# supply1.net
KiCad netlist of a schematic drawn in EAGLE
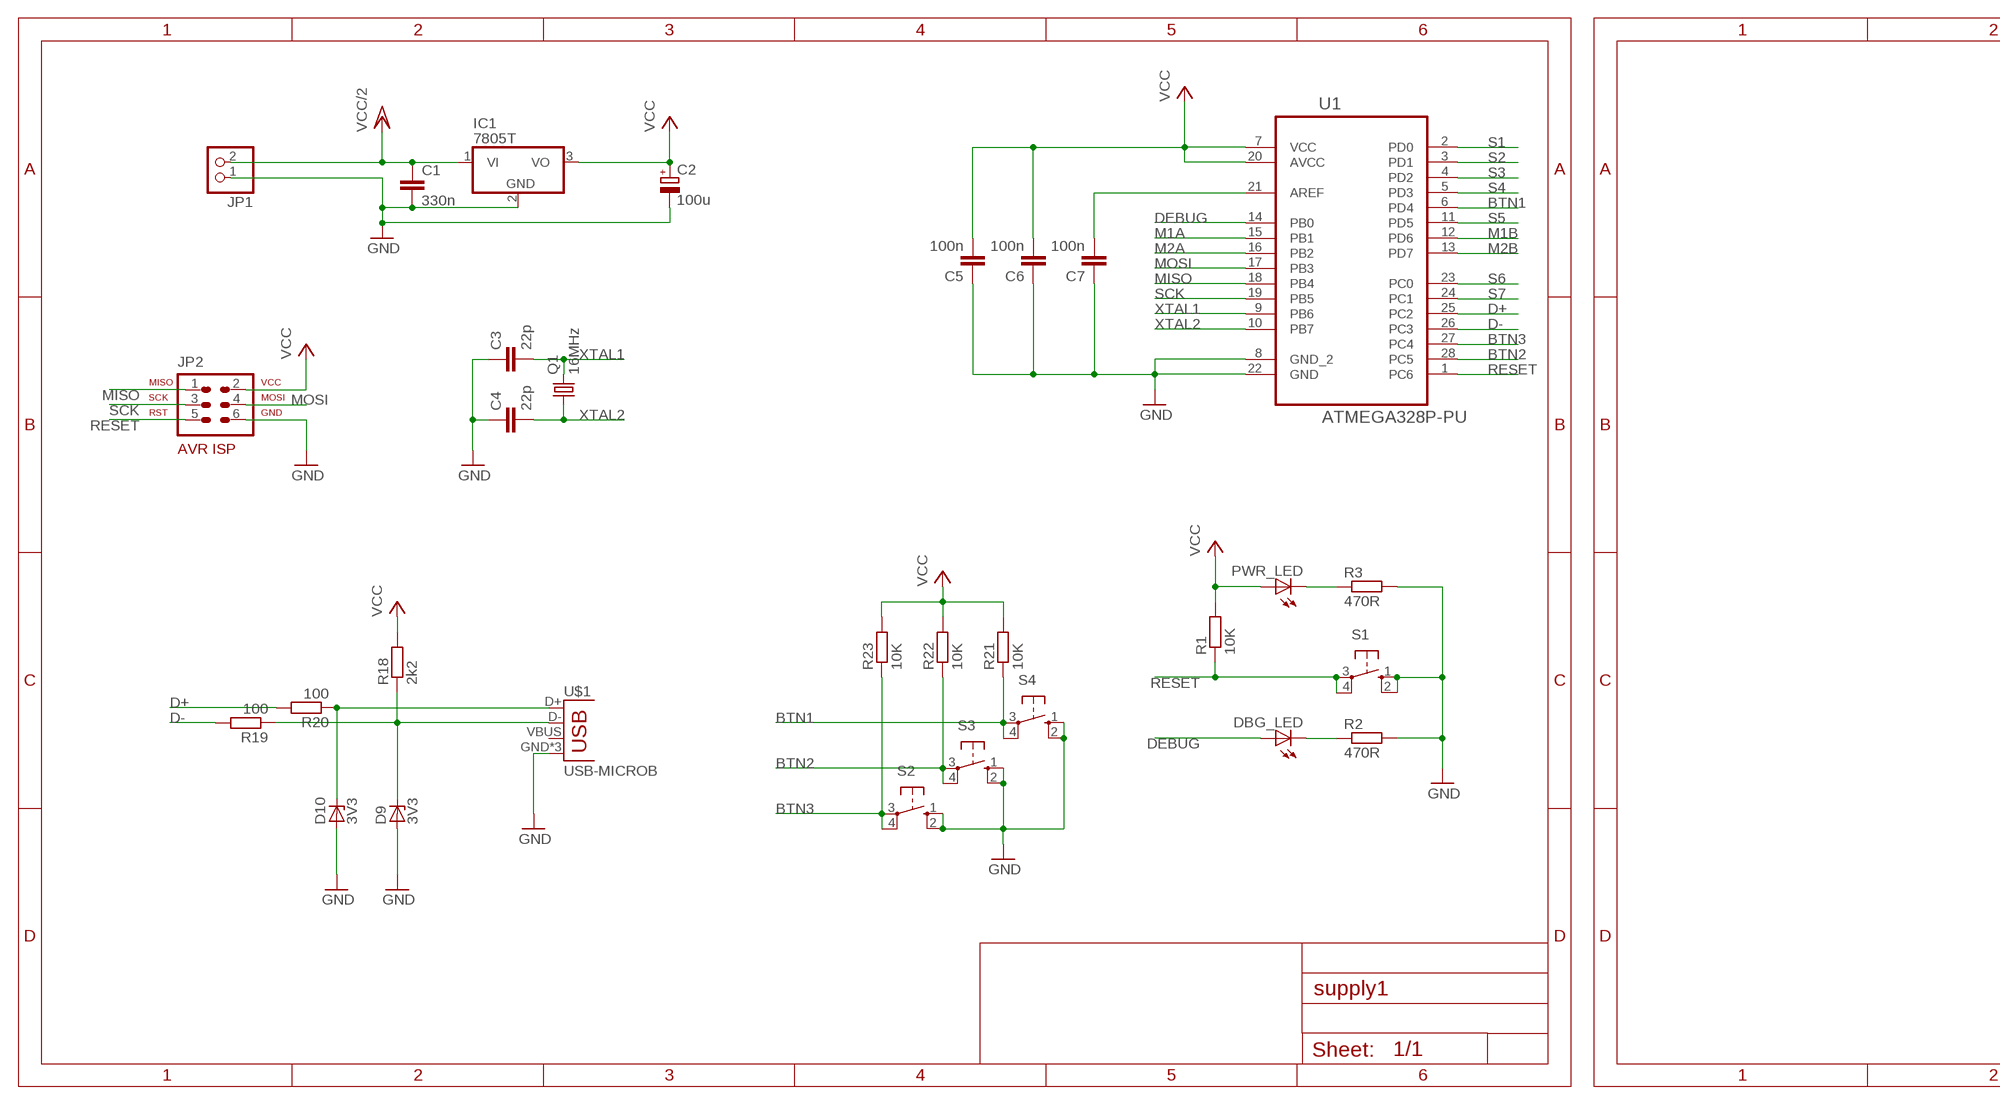
[diagram p0: schematic, sheet 1, part 1 of 2]
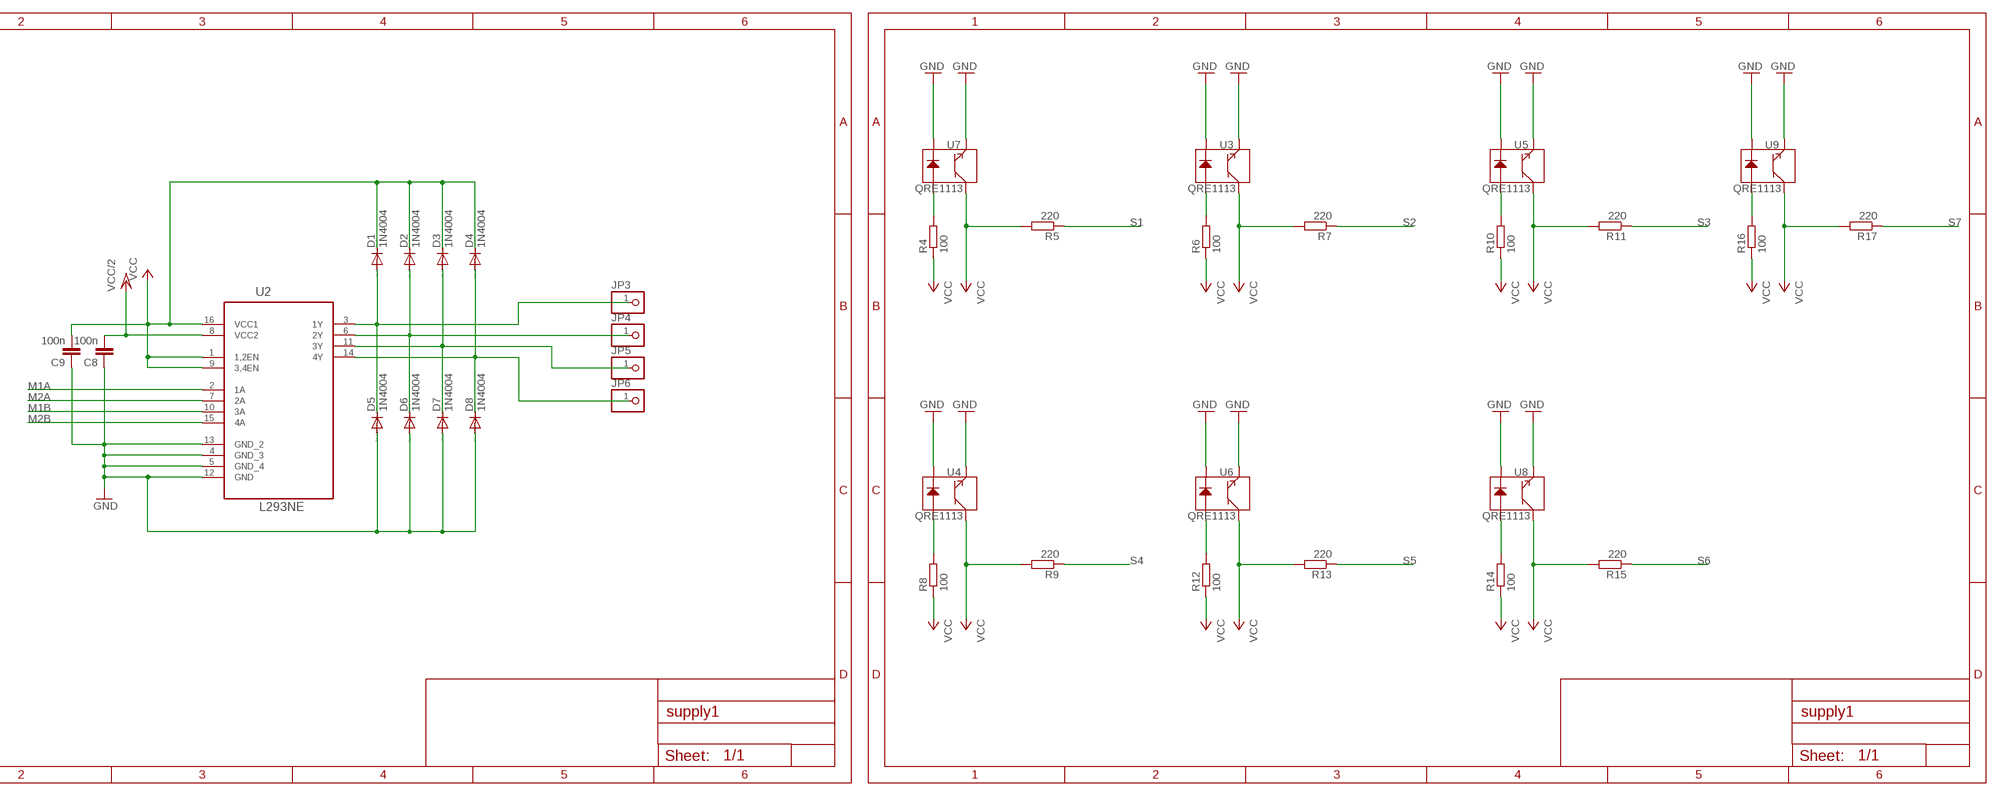
[diagram p1: schematic, sheet 1, part 2 of 2]

(export (version "E")
  (design (tool "Eeschema 10.0.6"))
  (components
    (comp (ref "C1")
      (value "330n")
      (footprint "eagle-import:C1206K")
      (libsource (lib "eagle-import") (part "C-EUC1206K"))
    )
    (comp (ref "C2")
      (value "100u")
      (footprint "eagle-import:E2,5-5")
      (libsource (lib "eagle-import") (part "CPOL-EUE2.5-5"))
    )
    (comp (ref "C3")
      (value "22p")
      (footprint "eagle-import:C0805K")
      (libsource (lib "eagle-import") (part "C-EUC0805K"))
    )
    (comp (ref "C4")
      (value "22p")
      (footprint "eagle-import:C0805K")
      (libsource (lib "eagle-import") (part "C-EUC0805K"))
    )
    (comp (ref "C5")
      (value "100n")
      (footprint "eagle-import:C0805K")
      (libsource (lib "eagle-import") (part "C-EUC0805K"))
    )
    (comp (ref "C6")
      (value "100n")
      (footprint "eagle-import:C0805K")
      (libsource (lib "eagle-import") (part "C-EUC0805K"))
    )
    (comp (ref "C7")
      (value "100n")
      (footprint "eagle-import:C0805K")
      (libsource (lib "eagle-import") (part "C-EUC0805K"))
    )
    (comp (ref "C8")
      (value "100n")
      (footprint "eagle-import:C0805K")
      (libsource (lib "eagle-import") (part "C-EUC0805K"))
    )
    (comp (ref "C9")
      (value "100n")
      (footprint "eagle-import:C0805K")
      (libsource (lib "eagle-import") (part "C-EUC0805K"))
    )
    (comp (ref "D1")
      (value "1N4004")
      (footprint "eagle-import:DO41-10")
      (libsource (lib "eagle-import") (part "1N4004"))
    )
    (comp (ref "D2")
      (value "1N4004")
      (footprint "eagle-import:DO41-10")
      (libsource (lib "eagle-import") (part "1N4004"))
    )
    (comp (ref "D3")
      (value "1N4004")
      (footprint "eagle-import:DO41-10")
      (libsource (lib "eagle-import") (part "1N4004"))
    )
    (comp (ref "D4")
      (value "1N4004")
      (footprint "eagle-import:DO41-10")
      (libsource (lib "eagle-import") (part "1N4004"))
    )
    (comp (ref "D5")
      (value "1N4004")
      (footprint "eagle-import:DO41-10")
      (libsource (lib "eagle-import") (part "1N4004"))
    )
    (comp (ref "D6")
      (value "1N4004")
      (footprint "eagle-import:DO41-10")
      (libsource (lib "eagle-import") (part "1N4004"))
    )
    (comp (ref "D7")
      (value "1N4004")
      (footprint "eagle-import:DO41-10")
      (libsource (lib "eagle-import") (part "1N4004"))
    )
    (comp (ref "D8")
      (value "1N4004")
      (footprint "eagle-import:DO41-10")
      (libsource (lib "eagle-import") (part "1N4004"))
    )
    (comp (ref "D9")
      (value "3V3")
      (footprint "eagle-import:DO41Z10")
      (libsource (lib "eagle-import") (part "ZENER-DIODEDO41Z10"))
    )
    (comp (ref "D10")
      (value "3V3")
      (footprint "eagle-import:DO41Z10")
      (libsource (lib "eagle-import") (part "ZENER-DIODEDO41Z10"))
    )
    (comp (ref "DBG_LED")
      (value "LED5MM")
      (footprint "eagle-import:LED5MM")
      (libsource (lib "eagle-import") (part "LED5MM"))
    )
    (comp (ref "IC1")
      (value "7805T")
      (footprint "eagle-import:TO220H")
      (libsource (lib "eagle-import") (part "78T05"))
    )
    (comp (ref "JP1")
      (value "PINHD-1X2")
      (footprint "eagle-import:1X02")
      (libsource (lib "eagle-import") (part "PINHD-1X2"))
    )
    (comp (ref "JP2")
      (value "AVR-ISP-6VERT")
      (footprint "eagle-import:AVR-ISP-6")
      (libsource (lib "eagle-import") (part "AVR-ISP-6VERT"))
    )
    (comp (ref "JP3")
      (value "PINHD-1X1")
      (footprint "eagle-import:1X01")
      (libsource (lib "eagle-import") (part "PINHD-1X1"))
    )
    (comp (ref "JP4")
      (value "PINHD-1X1")
      (footprint "eagle-import:1X01")
      (libsource (lib "eagle-import") (part "PINHD-1X1"))
    )
    (comp (ref "JP5")
      (value "PINHD-1X1")
      (footprint "eagle-import:1X01")
      (libsource (lib "eagle-import") (part "PINHD-1X1"))
    )
    (comp (ref "JP6")
      (value "PINHD-1X1")
      (footprint "eagle-import:1X01")
      (libsource (lib "eagle-import") (part "PINHD-1X1"))
    )
    (comp (ref "PWR_LED")
      (value "LED5MM")
      (footprint "eagle-import:LED5MM")
      (libsource (lib "eagle-import") (part "LED5MM"))
    )
    (comp (ref "Q1")
      (value "16MHz")
      (footprint "eagle-import:HC49_S")
      (libsource (lib "eagle-import") (part "CRYSTALHC49S"))
    )
    (comp (ref "R1")
      (value "10K")
      (footprint "eagle-import:M0805")
      (libsource (lib "eagle-import") (part "R-EU_M0805"))
    )
    (comp (ref "R2")
      (value "470R")
      (footprint "eagle-import:M0805")
      (libsource (lib "eagle-import") (part "R-EU_M0805"))
    )
    (comp (ref "R3")
      (value "470R")
      (footprint "eagle-import:M0805")
      (libsource (lib "eagle-import") (part "R-EU_M0805"))
    )
    (comp (ref "R4")
      (value "100")
      (footprint "eagle-import:M0805")
      (libsource (lib "eagle-import") (part "R-EU_M0805"))
    )
    (comp (ref "R5")
      (value "220")
      (footprint "eagle-import:M0805")
      (libsource (lib "eagle-import") (part "R-EU_M0805"))
    )
    (comp (ref "R6")
      (value "100")
      (footprint "eagle-import:M0805")
      (libsource (lib "eagle-import") (part "R-EU_M0805"))
    )
    (comp (ref "R7")
      (value "220")
      (footprint "eagle-import:M0805")
      (libsource (lib "eagle-import") (part "R-EU_M0805"))
    )
    (comp (ref "R8")
      (value "100")
      (footprint "eagle-import:M0805")
      (libsource (lib "eagle-import") (part "R-EU_M0805"))
    )
    (comp (ref "R9")
      (value "220")
      (footprint "eagle-import:M0805")
      (libsource (lib "eagle-import") (part "R-EU_M0805"))
    )
    (comp (ref "R10")
      (value "100")
      (footprint "eagle-import:M0805")
      (libsource (lib "eagle-import") (part "R-EU_M0805"))
    )
    (comp (ref "R11")
      (value "220")
      (footprint "eagle-import:M0805")
      (libsource (lib "eagle-import") (part "R-EU_M0805"))
    )
    (comp (ref "R12")
      (value "100")
      (footprint "eagle-import:M0805")
      (libsource (lib "eagle-import") (part "R-EU_M0805"))
    )
    (comp (ref "R13")
      (value "220")
      (footprint "eagle-import:M0805")
      (libsource (lib "eagle-import") (part "R-EU_M0805"))
    )
    (comp (ref "R14")
      (value "100")
      (footprint "eagle-import:M0805")
      (libsource (lib "eagle-import") (part "R-EU_M0805"))
    )
    (comp (ref "R15")
      (value "220")
      (footprint "eagle-import:M0805")
      (libsource (lib "eagle-import") (part "R-EU_M0805"))
    )
    (comp (ref "R16")
      (value "100")
      (footprint "eagle-import:M0805")
      (libsource (lib "eagle-import") (part "R-EU_M0805"))
    )
    (comp (ref "R17")
      (value "220")
      (footprint "eagle-import:M0805")
      (libsource (lib "eagle-import") (part "R-EU_M0805"))
    )
    (comp (ref "R18")
      (value "2k2")
      (footprint "eagle-import:M0805")
      (libsource (lib "eagle-import") (part "R-EU_M0805"))
    )
    (comp (ref "R19")
      (value "100")
      (footprint "eagle-import:M0805")
      (libsource (lib "eagle-import") (part "R-EU_M0805"))
    )
    (comp (ref "R20")
      (value "100")
      (footprint "eagle-import:M0805")
      (libsource (lib "eagle-import") (part "R-EU_M0805"))
    )
    (comp (ref "R21")
      (value "10K")
      (footprint "eagle-import:M0805")
      (libsource (lib "eagle-import") (part "R-EU_M0805"))
    )
    (comp (ref "R22")
      (value "10K")
      (footprint "eagle-import:M0805")
      (libsource (lib "eagle-import") (part "R-EU_M0805"))
    )
    (comp (ref "R23")
      (value "10K")
      (footprint "eagle-import:M0805")
      (libsource (lib "eagle-import") (part "R-EU_M0805"))
    )
    (comp (ref "S1")
      (value "10-XX")
      (footprint "eagle-import:B3F-10XX")
      (fields (field (name "MPN") "B3F-1000"))
      (libsource (lib "eagle-import") (part "10-XX"))
    )
    (comp (ref "S2")
      (value "10-XX")
      (footprint "eagle-import:B3F-10XX")
      (fields (field (name "MPN") "B3F-1000"))
      (libsource (lib "eagle-import") (part "10-XX"))
    )
    (comp (ref "S3")
      (value "10-XX")
      (footprint "eagle-import:B3F-10XX")
      (fields (field (name "MPN") "B3F-1000"))
      (libsource (lib "eagle-import") (part "10-XX"))
    )
    (comp (ref "S4")
      (value "10-XX")
      (footprint "eagle-import:B3F-10XX")
      (fields (field (name "MPN") "B3F-1000"))
      (libsource (lib "eagle-import") (part "10-XX"))
    )
    (comp (ref "U$1")
      (value "USB-MICROB")
      (footprint "eagle-import:USB-MICROB")
      (libsource (lib "eagle-import") (part "USB-MICROB"))
    )
    (comp (ref "U1")
      (value "ATMEGA328P-PU")
      (footprint "eagle-import:DIP254P762X457-28")
      (libsource (lib "eagle-import") (part "ATMEGA328P-PU"))
    )
    (comp (ref "U2")
      (value "L293NE")
      (footprint "eagle-import:DIP254P762X508-16")
      (libsource (lib "eagle-import") (part "L293NE"))
    )
    (comp (ref "U3")
      (value "QRE1113")
      (footprint "eagle-import:QRE1113")
      (libsource (lib "eagle-import") (part "QRE1113"))
    )
    (comp (ref "U4")
      (value "QRE1113")
      (footprint "eagle-import:QRE1113")
      (libsource (lib "eagle-import") (part "QRE1113"))
    )
    (comp (ref "U5")
      (value "QRE1113")
      (footprint "eagle-import:QRE1113")
      (libsource (lib "eagle-import") (part "QRE1113"))
    )
    (comp (ref "U6")
      (value "QRE1113")
      (footprint "eagle-import:QRE1113")
      (libsource (lib "eagle-import") (part "QRE1113"))
    )
    (comp (ref "U7")
      (value "QRE1113")
      (footprint "eagle-import:QRE1113")
      (libsource (lib "eagle-import") (part "QRE1113"))
    )
    (comp (ref "U8")
      (value "QRE1113")
      (footprint "eagle-import:QRE1113")
      (libsource (lib "eagle-import") (part "QRE1113"))
    )
    (comp (ref "U9")
      (value "QRE1113")
      (footprint "eagle-import:QRE1113")
      (libsource (lib "eagle-import") (part "QRE1113"))
    )
  )
  (nets
    (net (code "1") (name "/BTN1") (class "Default")
      (node (ref "R21") (pin "1") (pinfunction "1_1") (pintype "passive"))
      (node (ref "S4") (pin "3") (pinfunction "P_3") (pintype "passive"))
      (node (ref "S4") (pin "4") (pinfunction "P1_4") (pintype "passive"))
      (node (ref "U1") (pin "6") (pinfunction "PD4_6") (pintype "bidirectional"))
    )
    (net (code "2") (name "/BTN2") (class "Default")
      (node (ref "R22") (pin "1") (pinfunction "1_1") (pintype "passive"))
      (node (ref "S3") (pin "3") (pinfunction "P_3") (pintype "passive"))
      (node (ref "S3") (pin "4") (pinfunction "P1_4") (pintype "passive"))
      (node (ref "U1") (pin "28") (pinfunction "PC5_28") (pintype "bidirectional"))
    )
    (net (code "3") (name "/BTN3") (class "Default")
      (node (ref "R23") (pin "1") (pinfunction "1_1") (pintype "passive"))
      (node (ref "S2") (pin "3") (pinfunction "P_3") (pintype "passive"))
      (node (ref "S2") (pin "4") (pinfunction "P1_4") (pintype "passive"))
      (node (ref "U1") (pin "27") (pinfunction "PC4_27") (pintype "bidirectional"))
    )
    (net (code "4") (name "/D+") (class "Default")
      (node (ref "R20") (pin "2") (pinfunction "2_2") (pintype "passive"))
      (node (ref "U1") (pin "25") (pinfunction "PC2_25") (pintype "bidirectional"))
    )
    (net (code "5") (name "/D-") (class "Default")
      (node (ref "R19") (pin "2") (pinfunction "2_2") (pintype "passive"))
      (node (ref "U1") (pin "26") (pinfunction "PC3_26") (pintype "bidirectional"))
    )
    (net (code "6") (name "/DEBUG") (class "Default")
      (node (ref "DBG_LED") (pin "A") (pinfunction "A_A") (pintype "passive"))
      (node (ref "U1") (pin "14") (pinfunction "PB0_14") (pintype "bidirectional"))
    )
    (net (code "7") (name "/M1A") (class "Default")
      (node (ref "U1") (pin "15") (pinfunction "PB1_15") (pintype "bidirectional"))
      (node (ref "U2") (pin "2") (pinfunction "1A_2") (pintype "input"))
    )
    (net (code "8") (name "/M1B") (class "Default")
      (node (ref "U1") (pin "12") (pinfunction "PD6_12") (pintype "bidirectional"))
      (node (ref "U2") (pin "10") (pinfunction "3A_10") (pintype "input"))
    )
    (net (code "9") (name "/M2A") (class "Default")
      (node (ref "U1") (pin "16") (pinfunction "PB2_16") (pintype "bidirectional"))
      (node (ref "U2") (pin "7") (pinfunction "2A_7") (pintype "input"))
    )
    (net (code "10") (name "/M2B") (class "Default")
      (node (ref "U1") (pin "13") (pinfunction "PD7_13") (pintype "bidirectional"))
      (node (ref "U2") (pin "15") (pinfunction "4A_15") (pintype "input"))
    )
    (net (code "11") (name "/MISO") (class "Default")
      (node (ref "JP2") (pin "1") (pinfunction "1_1") (pintype "passive"))
      (node (ref "U1") (pin "18") (pinfunction "PB4_18") (pintype "bidirectional"))
    )
    (net (code "12") (name "/MOSI") (class "Default")
      (node (ref "JP2") (pin "4") (pinfunction "4_4") (pintype "passive"))
      (node (ref "U1") (pin "17") (pinfunction "PB3_17") (pintype "bidirectional"))
    )
    (net (code "13") (name "/RESET") (class "Default")
      (node (ref "JP2") (pin "5") (pinfunction "5_5") (pintype "passive"))
      (node (ref "R1") (pin "1") (pinfunction "1_1") (pintype "passive"))
      (node (ref "S1") (pin "3") (pinfunction "P_3") (pintype "passive"))
      (node (ref "S1") (pin "4") (pinfunction "P1_4") (pintype "passive"))
      (node (ref "U1") (pin "1") (pinfunction "PC6_1") (pintype "bidirectional"))
    )
    (net (code "14") (name "/S1") (class "Default")
      (node (ref "R5") (pin "1") (pinfunction "1_1") (pintype "passive"))
      (node (ref "U1") (pin "2") (pinfunction "PD0_2") (pintype "bidirectional"))
    )
    (net (code "15") (name "/S2") (class "Default")
      (node (ref "R7") (pin "1") (pinfunction "1_1") (pintype "passive"))
      (node (ref "U1") (pin "3") (pinfunction "PD1_3") (pintype "bidirectional"))
    )
    (net (code "16") (name "/S3") (class "Default")
      (node (ref "R11") (pin "1") (pinfunction "1_1") (pintype "passive"))
      (node (ref "U1") (pin "4") (pinfunction "PD2_4") (pintype "bidirectional"))
    )
    (net (code "17") (name "/S4") (class "Default")
      (node (ref "R9") (pin "1") (pinfunction "1_1") (pintype "passive"))
      (node (ref "U1") (pin "5") (pinfunction "PD3_5") (pintype "bidirectional"))
    )
    (net (code "18") (name "/S5") (class "Default")
      (node (ref "R13") (pin "1") (pinfunction "1_1") (pintype "passive"))
      (node (ref "U1") (pin "11") (pinfunction "PD5_11") (pintype "bidirectional"))
    )
    (net (code "19") (name "/S6") (class "Default")
      (node (ref "R15") (pin "1") (pinfunction "1_1") (pintype "passive"))
      (node (ref "U1") (pin "23") (pinfunction "PC0_23") (pintype "bidirectional"))
    )
    (net (code "20") (name "/S7") (class "Default")
      (node (ref "R17") (pin "1") (pinfunction "1_1") (pintype "passive"))
      (node (ref "U1") (pin "24") (pinfunction "PC1_24") (pintype "bidirectional"))
    )
    (net (code "21") (name "/SCK") (class "Default")
      (node (ref "JP2") (pin "3") (pinfunction "3_3") (pintype "passive"))
      (node (ref "U1") (pin "19") (pinfunction "PB5_19") (pintype "bidirectional"))
    )
    (net (code "22") (name "/XTAL1") (class "Default")
      (node (ref "C3") (pin "2") (pinfunction "2_2") (pintype "passive"))
      (node (ref "Q1") (pin "2") (pinfunction "2_2") (pintype "passive"))
      (node (ref "U1") (pin "9") (pinfunction "PB6_9") (pintype "bidirectional"))
    )
    (net (code "23") (name "/XTAL2") (class "Default")
      (node (ref "C4") (pin "2") (pinfunction "2_2") (pintype "passive"))
      (node (ref "Q1") (pin "1") (pinfunction "1_1") (pintype "passive"))
      (node (ref "U1") (pin "10") (pinfunction "PB7_10") (pintype "bidirectional"))
    )
    (net (code "24") (name "GND") (class "Default")
      (node (ref "C1") (pin "2") (pinfunction "2_2") (pintype "passive"))
      (node (ref "C2") (pin "-") (pinfunction "-_-") (pintype "passive"))
      (node (ref "C3") (pin "1") (pinfunction "1_1") (pintype "passive"))
      (node (ref "C4") (pin "1") (pinfunction "1_1") (pintype "passive"))
      (node (ref "C5") (pin "1") (pinfunction "1_1") (pintype "passive"))
      (node (ref "C6") (pin "1") (pinfunction "1_1") (pintype "passive"))
      (node (ref "C7") (pin "1") (pinfunction "1_1") (pintype "passive"))
      (node (ref "C8") (pin "1") (pinfunction "1_1") (pintype "passive"))
      (node (ref "C9") (pin "1") (pinfunction "1_1") (pintype "passive"))
      (node (ref "D10") (pin "A") (pinfunction "A_A") (pintype "passive"))
      (node (ref "D5") (pin "A") (pinfunction "A_A") (pintype "passive"))
      (node (ref "D6") (pin "A") (pinfunction "A_A") (pintype "passive"))
      (node (ref "D7") (pin "A") (pinfunction "A_A") (pintype "passive"))
      (node (ref "D8") (pin "A") (pinfunction "A_A") (pintype "passive"))
      (node (ref "D9") (pin "A") (pinfunction "A_A") (pintype "passive"))
      (node (ref "IC1") (pin "2") (pinfunction "GND_2") (pintype "passive"))
      (node (ref "JP1") (pin "1") (pinfunction "1_1") (pintype "passive"))
      (node (ref "JP2") (pin "6") (pinfunction "6_6") (pintype "passive"))
      (node (ref "R2") (pin "2") (pinfunction "2_2") (pintype "passive"))
      (node (ref "R3") (pin "2") (pinfunction "2_2") (pintype "passive"))
      (node (ref "S1") (pin "1") (pinfunction "S_1") (pintype "passive"))
      (node (ref "S1") (pin "2") (pinfunction "S1_2") (pintype "passive"))
      (node (ref "S2") (pin "1") (pinfunction "S_1") (pintype "passive"))
      (node (ref "S2") (pin "2") (pinfunction "S1_2") (pintype "passive"))
      (node (ref "S3") (pin "1") (pinfunction "S_1") (pintype "passive"))
      (node (ref "S3") (pin "2") (pinfunction "S1_2") (pintype "passive"))
      (node (ref "S4") (pin "1") (pinfunction "S_1") (pintype "passive"))
      (node (ref "S4") (pin "2") (pinfunction "S1_2") (pintype "passive"))
      (node (ref "U$1") (pin "GND") (pinfunction "GND_GND") (pintype "bidirectional"))
      (node (ref "U$1") (pin "MT1") (pinfunction "GND_MT1") (pintype "bidirectional"))
      (node (ref "U$1") (pin "MT2") (pinfunction "GND_MT2") (pintype "bidirectional"))
      (node (ref "U1") (pin "22") (pinfunction "GND_22") (pintype "passive"))
      (node (ref "U1") (pin "8") (pinfunction "GND_2_8") (pintype "passive"))
      (node (ref "U2") (pin "12") (pinfunction "GND_12") (pintype "passive"))
      (node (ref "U2") (pin "13") (pinfunction "GND_2_13") (pintype "passive"))
      (node (ref "U2") (pin "4") (pinfunction "GND_3_4") (pintype "passive"))
      (node (ref "U2") (pin "5") (pinfunction "GND_4_5") (pintype "passive"))
      (node (ref "U3") (pin "2") (pinfunction "K_2") (pintype "bidirectional"))
      (node (ref "U3") (pin "4") (pinfunction "E_4") (pintype "bidirectional"))
      (node (ref "U4") (pin "2") (pinfunction "K_2") (pintype "bidirectional"))
      (node (ref "U4") (pin "4") (pinfunction "E_4") (pintype "bidirectional"))
      (node (ref "U5") (pin "2") (pinfunction "K_2") (pintype "bidirectional"))
      (node (ref "U5") (pin "4") (pinfunction "E_4") (pintype "bidirectional"))
      (node (ref "U6") (pin "2") (pinfunction "K_2") (pintype "bidirectional"))
      (node (ref "U6") (pin "4") (pinfunction "E_4") (pintype "bidirectional"))
      (node (ref "U7") (pin "2") (pinfunction "K_2") (pintype "bidirectional"))
      (node (ref "U7") (pin "4") (pinfunction "E_4") (pintype "bidirectional"))
      (node (ref "U8") (pin "2") (pinfunction "K_2") (pintype "bidirectional"))
      (node (ref "U8") (pin "4") (pinfunction "E_4") (pintype "bidirectional"))
      (node (ref "U9") (pin "2") (pinfunction "K_2") (pintype "bidirectional"))
      (node (ref "U9") (pin "4") (pinfunction "E_4") (pintype "bidirectional"))
    )
    (net (code "25") (name "Net-(D9-PadC)") (class "Default")
      (node (ref "D9") (pin "C") (pinfunction "C_C") (pintype "passive"))
      (node (ref "R18") (pin "1") (pinfunction "1_1") (pintype "passive"))
      (node (ref "R19") (pin "1") (pinfunction "1_1") (pintype "passive"))
      (node (ref "U$1") (pin "D-") (pinfunction "D-_D-") (pintype "bidirectional"))
    )
    (net (code "26") (name "Net-(D10-PadC)") (class "Default")
      (node (ref "D10") (pin "C") (pinfunction "C_C") (pintype "passive"))
      (node (ref "R20") (pin "1") (pinfunction "1_1") (pintype "passive"))
      (node (ref "U$1") (pin "D+") (pinfunction "D+_D+") (pintype "bidirectional"))
    )
    (net (code "27") (name "Net-(DBG_LED-C)") (class "Default")
      (node (ref "DBG_LED") (pin "K") (pinfunction "C_K") (pintype "passive"))
      (node (ref "R2") (pin "1") (pinfunction "1_1") (pintype "passive"))
    )
    (net (code "28") (name "Net-(PWR_LED-C)") (class "Default")
      (node (ref "PWR_LED") (pin "K") (pinfunction "C_K") (pintype "passive"))
      (node (ref "R3") (pin "1") (pinfunction "1_1") (pintype "passive"))
    )
    (net (code "29") (name "Net-(U1-AREF)") (class "Default")
      (node (ref "C7") (pin "2") (pinfunction "2_2") (pintype "passive"))
      (node (ref "U1") (pin "21") (pinfunction "AREF_21") (pintype "input"))
    )
    (net (code "30") (name "Net-(U2-1Y)") (class "Default")
      (node (ref "D1") (pin "A") (pinfunction "A_A") (pintype "passive"))
      (node (ref "D5") (pin "C") (pinfunction "C_C") (pintype "passive"))
      (node (ref "JP3") (pin "1") (pinfunction "1_1") (pintype "passive"))
      (node (ref "U2") (pin "3") (pinfunction "1Y_3") (pintype "output"))
    )
    (net (code "31") (name "Net-(U2-2Y)") (class "Default")
      (node (ref "D2") (pin "A") (pinfunction "A_A") (pintype "passive"))
      (node (ref "D6") (pin "C") (pinfunction "C_C") (pintype "passive"))
      (node (ref "JP4") (pin "1") (pinfunction "1_1") (pintype "passive"))
      (node (ref "U2") (pin "6") (pinfunction "2Y_6") (pintype "output"))
    )
    (net (code "32") (name "Net-(U2-3Y)") (class "Default")
      (node (ref "D3") (pin "A") (pinfunction "A_A") (pintype "passive"))
      (node (ref "D7") (pin "C") (pinfunction "C_C") (pintype "passive"))
      (node (ref "JP5") (pin "1") (pinfunction "1_1") (pintype "passive"))
      (node (ref "U2") (pin "11") (pinfunction "3Y_11") (pintype "output"))
    )
    (net (code "33") (name "Net-(U2-4Y)") (class "Default")
      (node (ref "D4") (pin "A") (pinfunction "A_A") (pintype "passive"))
      (node (ref "D8") (pin "C") (pinfunction "C_C") (pintype "passive"))
      (node (ref "JP6") (pin "1") (pinfunction "1_1") (pintype "passive"))
      (node (ref "U2") (pin "14") (pinfunction "4Y_14") (pintype "output"))
    )
    (net (code "34") (name "Net-(U3-A)") (class "Default")
      (node (ref "R6") (pin "2") (pinfunction "2_2") (pintype "passive"))
      (node (ref "U3") (pin "1") (pinfunction "A_1") (pintype "bidirectional"))
    )
    (net (code "35") (name "Net-(U4-A)") (class "Default")
      (node (ref "R8") (pin "2") (pinfunction "2_2") (pintype "passive"))
      (node (ref "U4") (pin "1") (pinfunction "A_1") (pintype "bidirectional"))
    )
    (net (code "36") (name "Net-(U5-A)") (class "Default")
      (node (ref "R10") (pin "2") (pinfunction "2_2") (pintype "passive"))
      (node (ref "U5") (pin "1") (pinfunction "A_1") (pintype "bidirectional"))
    )
    (net (code "37") (name "Net-(U6-A)") (class "Default")
      (node (ref "R12") (pin "2") (pinfunction "2_2") (pintype "passive"))
      (node (ref "U6") (pin "1") (pinfunction "A_1") (pintype "bidirectional"))
    )
    (net (code "38") (name "Net-(U7-A)") (class "Default")
      (node (ref "R4") (pin "2") (pinfunction "2_2") (pintype "passive"))
      (node (ref "U7") (pin "1") (pinfunction "A_1") (pintype "bidirectional"))
    )
    (net (code "39") (name "Net-(U8-A)") (class "Default")
      (node (ref "R14") (pin "2") (pinfunction "2_2") (pintype "passive"))
      (node (ref "U8") (pin "1") (pinfunction "A_1") (pintype "bidirectional"))
    )
    (net (code "40") (name "Net-(U9-A)") (class "Default")
      (node (ref "R16") (pin "2") (pinfunction "2_2") (pintype "passive"))
      (node (ref "U9") (pin "1") (pinfunction "A_1") (pintype "bidirectional"))
    )
    (net (code "41") (name "VCC") (class "Default")
      (node (ref "C2") (pin "+") (pinfunction "+_+") (pintype "passive"))
      (node (ref "C5") (pin "2") (pinfunction "2_2") (pintype "passive"))
      (node (ref "C6") (pin "2") (pinfunction "2_2") (pintype "passive"))
      (node (ref "C9") (pin "2") (pinfunction "2_2") (pintype "passive"))
      (node (ref "D1") (pin "C") (pinfunction "C_C") (pintype "passive"))
      (node (ref "D2") (pin "C") (pinfunction "C_C") (pintype "passive"))
      (node (ref "D3") (pin "C") (pinfunction "C_C") (pintype "passive"))
      (node (ref "D4") (pin "C") (pinfunction "C_C") (pintype "passive"))
      (node (ref "IC1") (pin "3") (pinfunction "VO_3") (pintype "passive"))
      (node (ref "JP2") (pin "2") (pinfunction "2_2") (pintype "passive"))
      (node (ref "PWR_LED") (pin "A") (pinfunction "A_A") (pintype "passive"))
      (node (ref "R1") (pin "2") (pinfunction "2_2") (pintype "passive"))
      (node (ref "R10") (pin "1") (pinfunction "1_1") (pintype "passive"))
      (node (ref "R11") (pin "2") (pinfunction "2_2") (pintype "passive"))
      (node (ref "R12") (pin "1") (pinfunction "1_1") (pintype "passive"))
      (node (ref "R13") (pin "2") (pinfunction "2_2") (pintype "passive"))
      (node (ref "R14") (pin "1") (pinfunction "1_1") (pintype "passive"))
      (node (ref "R15") (pin "2") (pinfunction "2_2") (pintype "passive"))
      (node (ref "R16") (pin "1") (pinfunction "1_1") (pintype "passive"))
      (node (ref "R17") (pin "2") (pinfunction "2_2") (pintype "passive"))
      (node (ref "R18") (pin "2") (pinfunction "2_2") (pintype "passive"))
      (node (ref "R21") (pin "2") (pinfunction "2_2") (pintype "passive"))
      (node (ref "R22") (pin "2") (pinfunction "2_2") (pintype "passive"))
      (node (ref "R23") (pin "2") (pinfunction "2_2") (pintype "passive"))
      (node (ref "R4") (pin "1") (pinfunction "1_1") (pintype "passive"))
      (node (ref "R5") (pin "2") (pinfunction "2_2") (pintype "passive"))
      (node (ref "R6") (pin "1") (pinfunction "1_1") (pintype "passive"))
      (node (ref "R7") (pin "2") (pinfunction "2_2") (pintype "passive"))
      (node (ref "R8") (pin "1") (pinfunction "1_1") (pintype "passive"))
      (node (ref "R9") (pin "2") (pinfunction "2_2") (pintype "passive"))
      (node (ref "U1") (pin "20") (pinfunction "AVCC_20") (pintype "power_in"))
      (node (ref "U1") (pin "7") (pinfunction "VCC_7") (pintype "power_in"))
      (node (ref "U2") (pin "1") (pinfunction "1,2EN_1") (pintype "input"))
      (node (ref "U2") (pin "16") (pinfunction "VCC1_16") (pintype "power_in"))
      (node (ref "U2") (pin "9") (pinfunction "3,4EN_9") (pintype "input"))
      (node (ref "U3") (pin "3") (pinfunction "C_3") (pintype "bidirectional"))
      (node (ref "U4") (pin "3") (pinfunction "C_3") (pintype "bidirectional"))
      (node (ref "U5") (pin "3") (pinfunction "C_3") (pintype "bidirectional"))
      (node (ref "U6") (pin "3") (pinfunction "C_3") (pintype "bidirectional"))
      (node (ref "U7") (pin "3") (pinfunction "C_3") (pintype "bidirectional"))
      (node (ref "U8") (pin "3") (pinfunction "C_3") (pintype "bidirectional"))
      (node (ref "U9") (pin "3") (pinfunction "C_3") (pintype "bidirectional"))
    )
    (net (code "42") (name "VCC{slash}2") (class "Default")
      (node (ref "C1") (pin "1") (pinfunction "1_1") (pintype "passive"))
      (node (ref "C8") (pin "2") (pinfunction "2_2") (pintype "passive"))
      (node (ref "IC1") (pin "1") (pinfunction "VI_1") (pintype "input"))
      (node (ref "JP1") (pin "2") (pinfunction "2_2") (pintype "passive"))
      (node (ref "U2") (pin "8") (pinfunction "VCC2_8") (pintype "power_in"))
    )
    (net (code "43") (name "unconnected-(U$1-PadVBUS)") (class "Default")
      (node (ref "U$1") (pin "VBUS") (pinfunction "VBUS_VBUS") (pintype "bidirectional"))
    )
  )
)
